# RIIM.net
KiCad netlist of a schematic drawn in Altium Designer
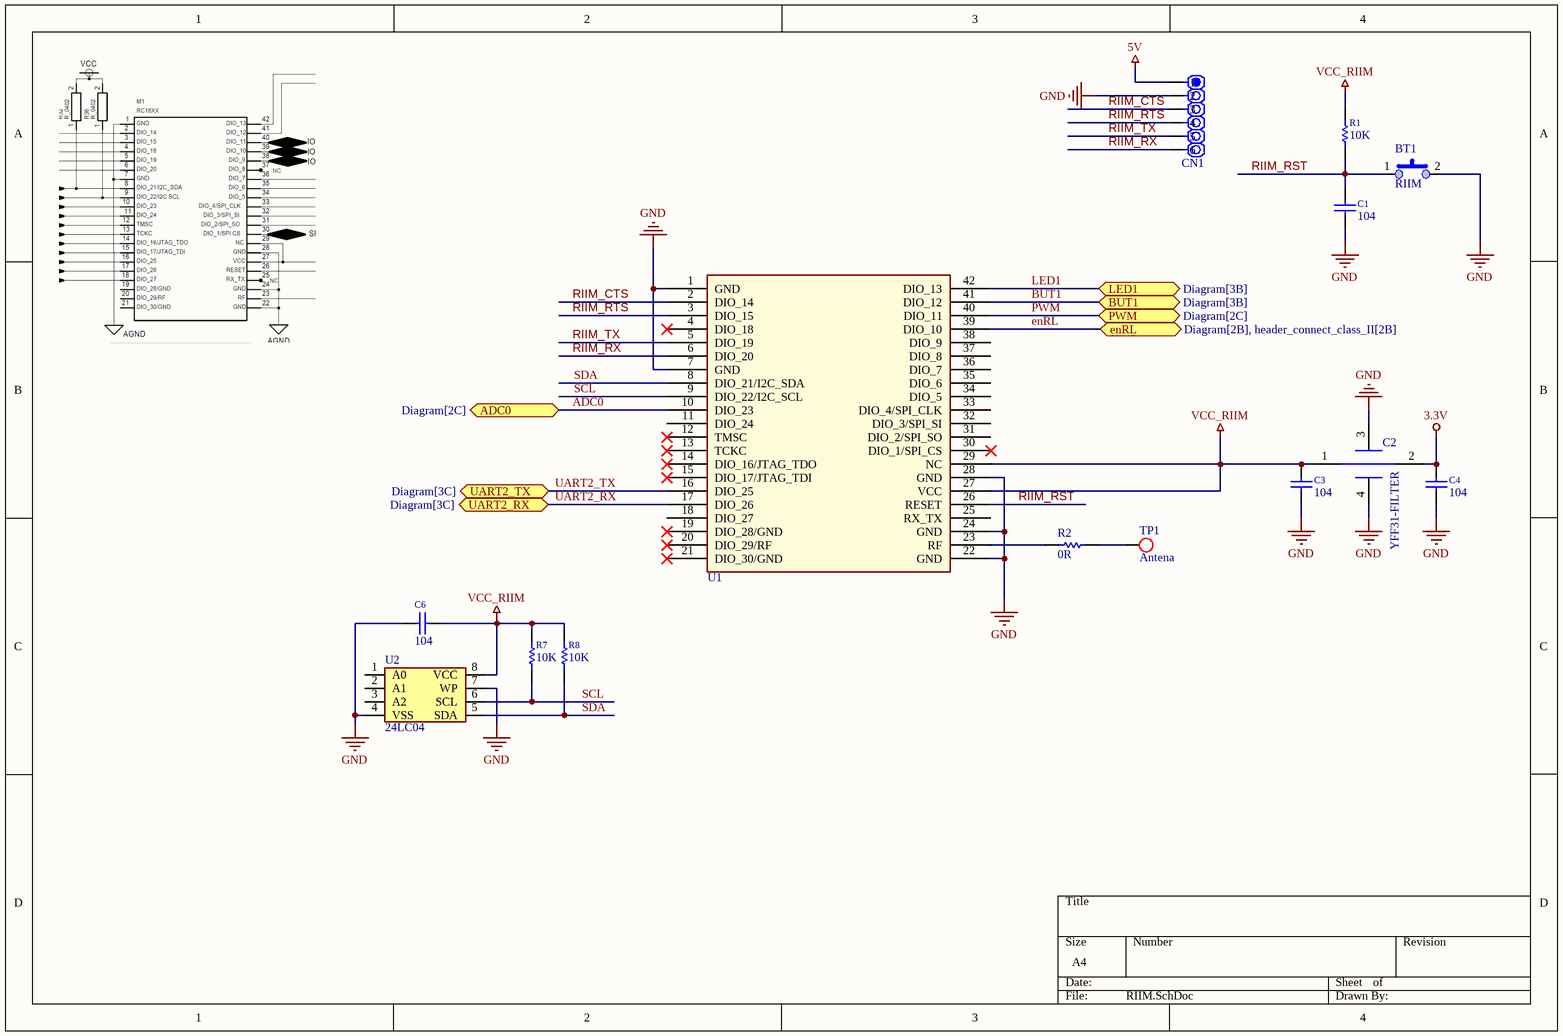
[diagram p0: RIIM.SchDoc]

(export (version "E")
  (design (tool "Eeschema 10.0.6"))
  (components
    (comp (ref "BT1")
      (value "RIIM")
      (footprint "B3U-1000P")
      (libsource (lib "VPMyLibrary") (part "Button_2p"))
    )
    (comp (ref "C1")
      (value "104")
      (footprint "C2012-0805")
      (description "Capacitor")
      (fields (field (name "PUBLISHER") "Hoang Nguyen"))
      (libsource (lib "VPMyLibrary") (part "Cap {lt}SMD{gt}"))
    )
    (comp (ref "C2")
      (value "YFF31-FILTER")
      (footprint "YFF31PC")
      (libsource (lib "VPMyLibrary") (part "YFF31-FILTER"))
    )
    (comp (ref "C3")
      (value "104")
      (footprint "C2012-0805")
      (description "Capacitor")
      (fields (field (name "PUBLISHER") "Hoang Nguyen"))
      (libsource (lib "VPMyLibrary") (part "Cap {lt}SMD{gt}"))
    )
    (comp (ref "C4")
      (value "104")
      (footprint "C2012-0805")
      (description "Capacitor")
      (fields (field (name "PUBLISHER") "Hoang Nguyen"))
      (libsource (lib "VPMyLibrary") (part "Cap {lt}SMD{gt}"))
    )
    (comp (ref "C6")
      (value "104")
      (footprint "C2012-0805")
      (description "Capacitor")
      (fields (field (name "PUBLISHER") "Hoang Nguyen"))
      (libsource (lib "VPMyLibrary") (part "Cap {lt}SMD{gt}"))
    )
    (comp (ref "CN1")
      (value "RIIM")
      (footprint "CON.HD1X6H")
      (description "Header 1x5")
      (fields (field (name "PUBLISHER") "Hoang Nguyen"))
      (libsource (lib "VPMyLibrary") (part "CON.HDR1x6"))
    )
    (comp (ref "R1")
      (value "10K")
      (footprint "R2012-0805")
      (description "Resistor")
      (fields (field (name "PUBLISHER") "Hoang Nguyen"))
      (libsource (lib "VPMyLibrary") (part "Resistor {lt}SMD{gt}"))
    )
    (comp (ref "R2") (value "0R") (footprint "R2012-0805") (libsource (lib "C15") (part "RES 1/4")))
    (comp (ref "R7")
      (value "10K")
      (footprint "R2012-0805")
      (description "Resistor")
      (fields (field (name "PUBLISHER") "Hoang Nguyen"))
      (libsource (lib "VPMyLibrary") (part "Resistor {lt}SMD{gt}"))
    )
    (comp (ref "R8")
      (value "10K")
      (footprint "R2012-0805")
      (description "Resistor")
      (fields (field (name "PUBLISHER") "Hoang Nguyen"))
      (libsource (lib "VPMyLibrary") (part "Resistor {lt}SMD{gt}"))
    )
    (comp (ref "TP1")
      (value "Antena")
      (footprint "TPoint")
      (libsource (lib "VPMyLibrary") (part "TestPoint"))
    )
    (comp (ref "U1")
      (value "RIIM_RC_1882")
      (footprint "RIIM_RC1882")
      (fields
        (field (name "MANUFACTURER") "Radiocrafts")
        (field (name "MANUFACTURER PART NUMBER") "RC1882HPCF-IPM")
      )
      (libsource (lib "VPMyLibrary") (part "RIIM_RC_1882"))
    )
    (comp (ref "U2") (value "24LC04") (footprint "SOIC8") (libsource (lib "VPMyLibrary") (part "24LC512")))
  )
  (nets
    (net (code "1") (name "/ADC0") (class "Default")
      (node (ref "U1") (pin "10") (pinfunction "DIO_23_10") (pintype "passive"))
    )
    (net (code "2") (name "/BUT1") (class "Default")
      (node (ref "U1") (pin "41") (pinfunction "DIO_12_41") (pintype "passive"))
    )
    (net (code "3") (name "/LED1") (class "Default")
      (node (ref "U1") (pin "42") (pinfunction "DIO_13_42") (pintype "passive"))
    )
    (net (code "4") (name "/PWM") (class "Default")
      (node (ref "U1") (pin "40") (pinfunction "DIO_11_40") (pintype "passive"))
    )
    (net (code "5") (name "/RIIM_CTS") (class "Default")
      (node (ref "CN1") (pin "3") (pinfunction "3_3") (pintype "passive"))
      (node (ref "U1") (pin "2") (pinfunction "DIO_14_2") (pintype "passive"))
    )
    (net (code "6") (name "/RIIM_RST") (class "Default")
      (node (ref "BT1") (pin "1") (pinfunction "1_1") (pintype "passive"))
      (node (ref "C1") (pin "1") (pinfunction "1_1") (pintype "passive"))
      (node (ref "R1") (pin "2") (pinfunction "2_2") (pintype "passive"))
      (node (ref "U1") (pin "26") (pinfunction "RESET_26") (pintype "passive"))
    )
    (net (code "7") (name "/RIIM_RTS") (class "Default")
      (node (ref "CN1") (pin "4") (pinfunction "4_4") (pintype "passive"))
      (node (ref "U1") (pin "3") (pinfunction "DIO_15_3") (pintype "passive"))
    )
    (net (code "8") (name "/RIIM_RX") (class "Default")
      (node (ref "CN1") (pin "6") (pinfunction "6_6") (pintype "passive"))
      (node (ref "U1") (pin "6") (pinfunction "DIO_20_6") (pintype "passive"))
    )
    (net (code "9") (name "/RIIM_TX") (class "Default")
      (node (ref "CN1") (pin "5") (pinfunction "5_5") (pintype "passive"))
      (node (ref "U1") (pin "5") (pinfunction "DIO_19_5") (pintype "passive"))
    )
    (net (code "10") (name "/SCL") (class "Default")
      (node (ref "R7") (pin "2") (pinfunction "2_2") (pintype "passive"))
      (node (ref "U1") (pin "9") (pinfunction "DIO_22/I2C_SCL_9") (pintype "passive"))
      (node (ref "U2") (pin "6") (pinfunction "SCL_6") (pintype "passive"))
    )
    (net (code "11") (name "/SDA") (class "Default")
      (node (ref "R8") (pin "2") (pinfunction "2_2") (pintype "passive"))
      (node (ref "U1") (pin "8") (pinfunction "DIO_21/I2C_SDA_8") (pintype "passive"))
      (node (ref "U2") (pin "5") (pinfunction "SDA_5") (pintype "passive"))
    )
    (net (code "12") (name "/UART2_RX") (class "Default")
      (node (ref "U1") (pin "17") (pinfunction "DIO_26_17") (pintype "passive"))
    )
    (net (code "13") (name "/UART2_TX") (class "Default")
      (node (ref "U1") (pin "16") (pinfunction "DIO_25_16") (pintype "passive"))
    )
    (net (code "14") (name "/enRL") (class "Default")
      (node (ref "U1") (pin "39") (pinfunction "DIO_10_39") (pintype "passive"))
    )
    (net (code "15") (name "3.3V") (class "Default")
      (node (ref "C2") (pin "2") (pinfunction "IN/OUT_2") (pintype "passive"))
      (node (ref "C4") (pin "1") (pinfunction "1_1") (pintype "passive"))
    )
    (net (code "16") (name "5V") (class "Default")
      (node (ref "CN1") (pin "1") (pinfunction "1_1") (pintype "passive"))
    )
    (net (code "17") (name "GND") (class "Default")
      (node (ref "BT1") (pin "2") (pinfunction "2_2") (pintype "passive"))
      (node (ref "C1") (pin "2") (pinfunction "2_2") (pintype "passive"))
      (node (ref "C2") (pin "3") (pinfunction "GND_3") (pintype "passive"))
      (node (ref "C2") (pin "4") (pinfunction "GND_4") (pintype "passive"))
      (node (ref "C3") (pin "2") (pinfunction "2_2") (pintype "passive"))
      (node (ref "C4") (pin "2") (pinfunction "2_2") (pintype "passive"))
      (node (ref "C6") (pin "1") (pinfunction "1_1") (pintype "passive"))
      (node (ref "CN1") (pin "2") (pinfunction "2_2") (pintype "passive"))
      (node (ref "U1") (pin "1") (pinfunction "GND_1") (pintype "passive"))
      (node (ref "U1") (pin "22") (pinfunction "GND_22") (pintype "passive"))
      (node (ref "U1") (pin "24") (pinfunction "GND_24") (pintype "passive"))
      (node (ref "U1") (pin "28") (pinfunction "GND_28") (pintype "passive"))
      (node (ref "U1") (pin "7") (pinfunction "GND_7") (pintype "passive"))
      (node (ref "U2") (pin "4") (pinfunction "VSS_4") (pintype "passive"))
      (node (ref "U2") (pin "7") (pinfunction "WP_7") (pintype "passive"))
    )
    (net (code "18") (name "Net-(R2-Pad1)") (class "Default")
      (node (ref "R2") (pin "1") (pintype "passive"))
      (node (ref "TP1") (pin "1") (pinfunction "1_1") (pintype "passive"))
    )
    (net (code "19") (name "Net-(U1-RF)") (class "Default")
      (node (ref "R2") (pin "2") (pintype "passive"))
      (node (ref "U1") (pin "23") (pinfunction "RF_23") (pintype "passive"))
    )
    (net (code "20") (name "VCC_RIIM") (class "Default")
      (node (ref "C2") (pin "1") (pinfunction "IN/OUT_1") (pintype "passive"))
      (node (ref "C3") (pin "1") (pinfunction "1_1") (pintype "passive"))
      (node (ref "C6") (pin "2") (pinfunction "2_2") (pintype "passive"))
      (node (ref "R1") (pin "1") (pinfunction "1_1") (pintype "passive"))
      (node (ref "R7") (pin "1") (pinfunction "1_1") (pintype "passive"))
      (node (ref "R8") (pin "1") (pinfunction "1_1") (pintype "passive"))
      (node (ref "U1") (pin "27") (pinfunction "VCC_27") (pintype "passive"))
      (node (ref "U1") (pin "29") (pinfunction "NC_29") (pintype "passive"))
      (node (ref "U2") (pin "8") (pinfunction "VCC_8") (pintype "passive"))
    )
    (net (code "21") (name "unconnected-(U1-DIO_1{slash}SPI_CS-Pad30)") (class "Default")
      (node (ref "U1") (pin "30") (pinfunction "DIO_1/SPI_CS_30") (pintype "passive+no_connect"))
    )
    (net (code "22") (name "unconnected-(U1-DIO_2{slash}SPI_SO-Pad31)") (class "Default")
      (node (ref "U1") (pin "31") (pinfunction "DIO_2/SPI_SO_31") (pintype "passive"))
    )
    (net (code "23") (name "unconnected-(U1-DIO_3{slash}SPI_SI-Pad32)") (class "Default")
      (node (ref "U1") (pin "32") (pinfunction "DIO_3/SPI_SI_32") (pintype "passive"))
    )
    (net (code "24") (name "unconnected-(U1-DIO_4{slash}SPI_CLK-Pad33)") (class "Default")
      (node (ref "U1") (pin "33") (pinfunction "DIO_4/SPI_CLK_33") (pintype "passive"))
    )
    (net (code "25") (name "unconnected-(U1-DIO_5-Pad34)") (class "Default")
      (node (ref "U1") (pin "34") (pinfunction "DIO_5_34") (pintype "passive"))
    )
    (net (code "26") (name "unconnected-(U1-DIO_6-Pad35)") (class "Default")
      (node (ref "U1") (pin "35") (pinfunction "DIO_6_35") (pintype "passive"))
    )
    (net (code "27") (name "unconnected-(U1-DIO_7-Pad36)") (class "Default")
      (node (ref "U1") (pin "36") (pinfunction "DIO_7_36") (pintype "passive"))
    )
    (net (code "28") (name "unconnected-(U1-DIO_8-Pad37)") (class "Default")
      (node (ref "U1") (pin "37") (pinfunction "DIO_8_37") (pintype "passive"))
    )
    (net (code "29") (name "unconnected-(U1-DIO_9-Pad38)") (class "Default")
      (node (ref "U1") (pin "38") (pinfunction "DIO_9_38") (pintype "passive"))
    )
    (net (code "30") (name "unconnected-(U1-DIO_16{slash}JTAG_TDO-Pad14)") (class "Default")
      (node (ref "U1") (pin "14") (pinfunction "DIO_16/JTAG_TDO_14") (pintype "passive+no_connect"))
    )
    (net (code "31") (name "unconnected-(U1-DIO_17{slash}JTAG_TDI-Pad15)") (class "Default")
      (node (ref "U1") (pin "15") (pinfunction "DIO_17/JTAG_TDI_15") (pintype "passive+no_connect"))
    )
    (net (code "32") (name "unconnected-(U1-DIO_18-Pad4)") (class "Default")
      (node (ref "U1") (pin "4") (pinfunction "DIO_18_4") (pintype "passive+no_connect"))
    )
    (net (code "33") (name "unconnected-(U1-DIO_24-Pad11)") (class "Default")
      (node (ref "U1") (pin "11") (pinfunction "DIO_24_11") (pintype "passive"))
    )
    (net (code "34") (name "unconnected-(U1-DIO_27-Pad18)") (class "Default")
      (node (ref "U1") (pin "18") (pinfunction "DIO_27_18") (pintype "passive"))
    )
    (net (code "35") (name "unconnected-(U1-DIO_28{slash}GND-Pad19)") (class "Default")
      (node (ref "U1") (pin "19") (pinfunction "DIO_28/GND_19") (pintype "passive+no_connect"))
    )
    (net (code "36") (name "unconnected-(U1-DIO_29{slash}RF-Pad20)") (class "Default")
      (node (ref "U1") (pin "20") (pinfunction "DIO_29/RF_20") (pintype "passive+no_connect"))
    )
    (net (code "37") (name "unconnected-(U1-DIO_30{slash}GND-Pad21)") (class "Default")
      (node (ref "U1") (pin "21") (pinfunction "DIO_30/GND_21") (pintype "passive+no_connect"))
    )
    (net (code "38") (name "unconnected-(U1-RX_TX-Pad25)") (class "Default")
      (node (ref "U1") (pin "25") (pinfunction "RX_TX_25") (pintype "passive"))
    )
    (net (code "39") (name "unconnected-(U1-TCKC-Pad13)") (class "Default")
      (node (ref "U1") (pin "13") (pinfunction "TCKC_13") (pintype "passive+no_connect"))
    )
    (net (code "40") (name "unconnected-(U1-TMSC-Pad12)") (class "Default")
      (node (ref "U1") (pin "12") (pinfunction "TMSC_12") (pintype "passive+no_connect"))
    )
    (net (code "41") (name "unconnected-(U2-A0-Pad1)") (class "Default")
      (node (ref "U2") (pin "1") (pinfunction "A0_1") (pintype "passive"))
    )
    (net (code "42") (name "unconnected-(U2-A1-Pad2)") (class "Default")
      (node (ref "U2") (pin "2") (pinfunction "A1_2") (pintype "passive"))
    )
    (net (code "43") (name "unconnected-(U2-A2-Pad3)") (class "Default")
      (node (ref "U2") (pin "3") (pinfunction "A2_3") (pintype "passive"))
    )
  )
)
